# ZX_UNO_Aplus2.net
KiCad netlist of a schematic drawn in Altium Designer
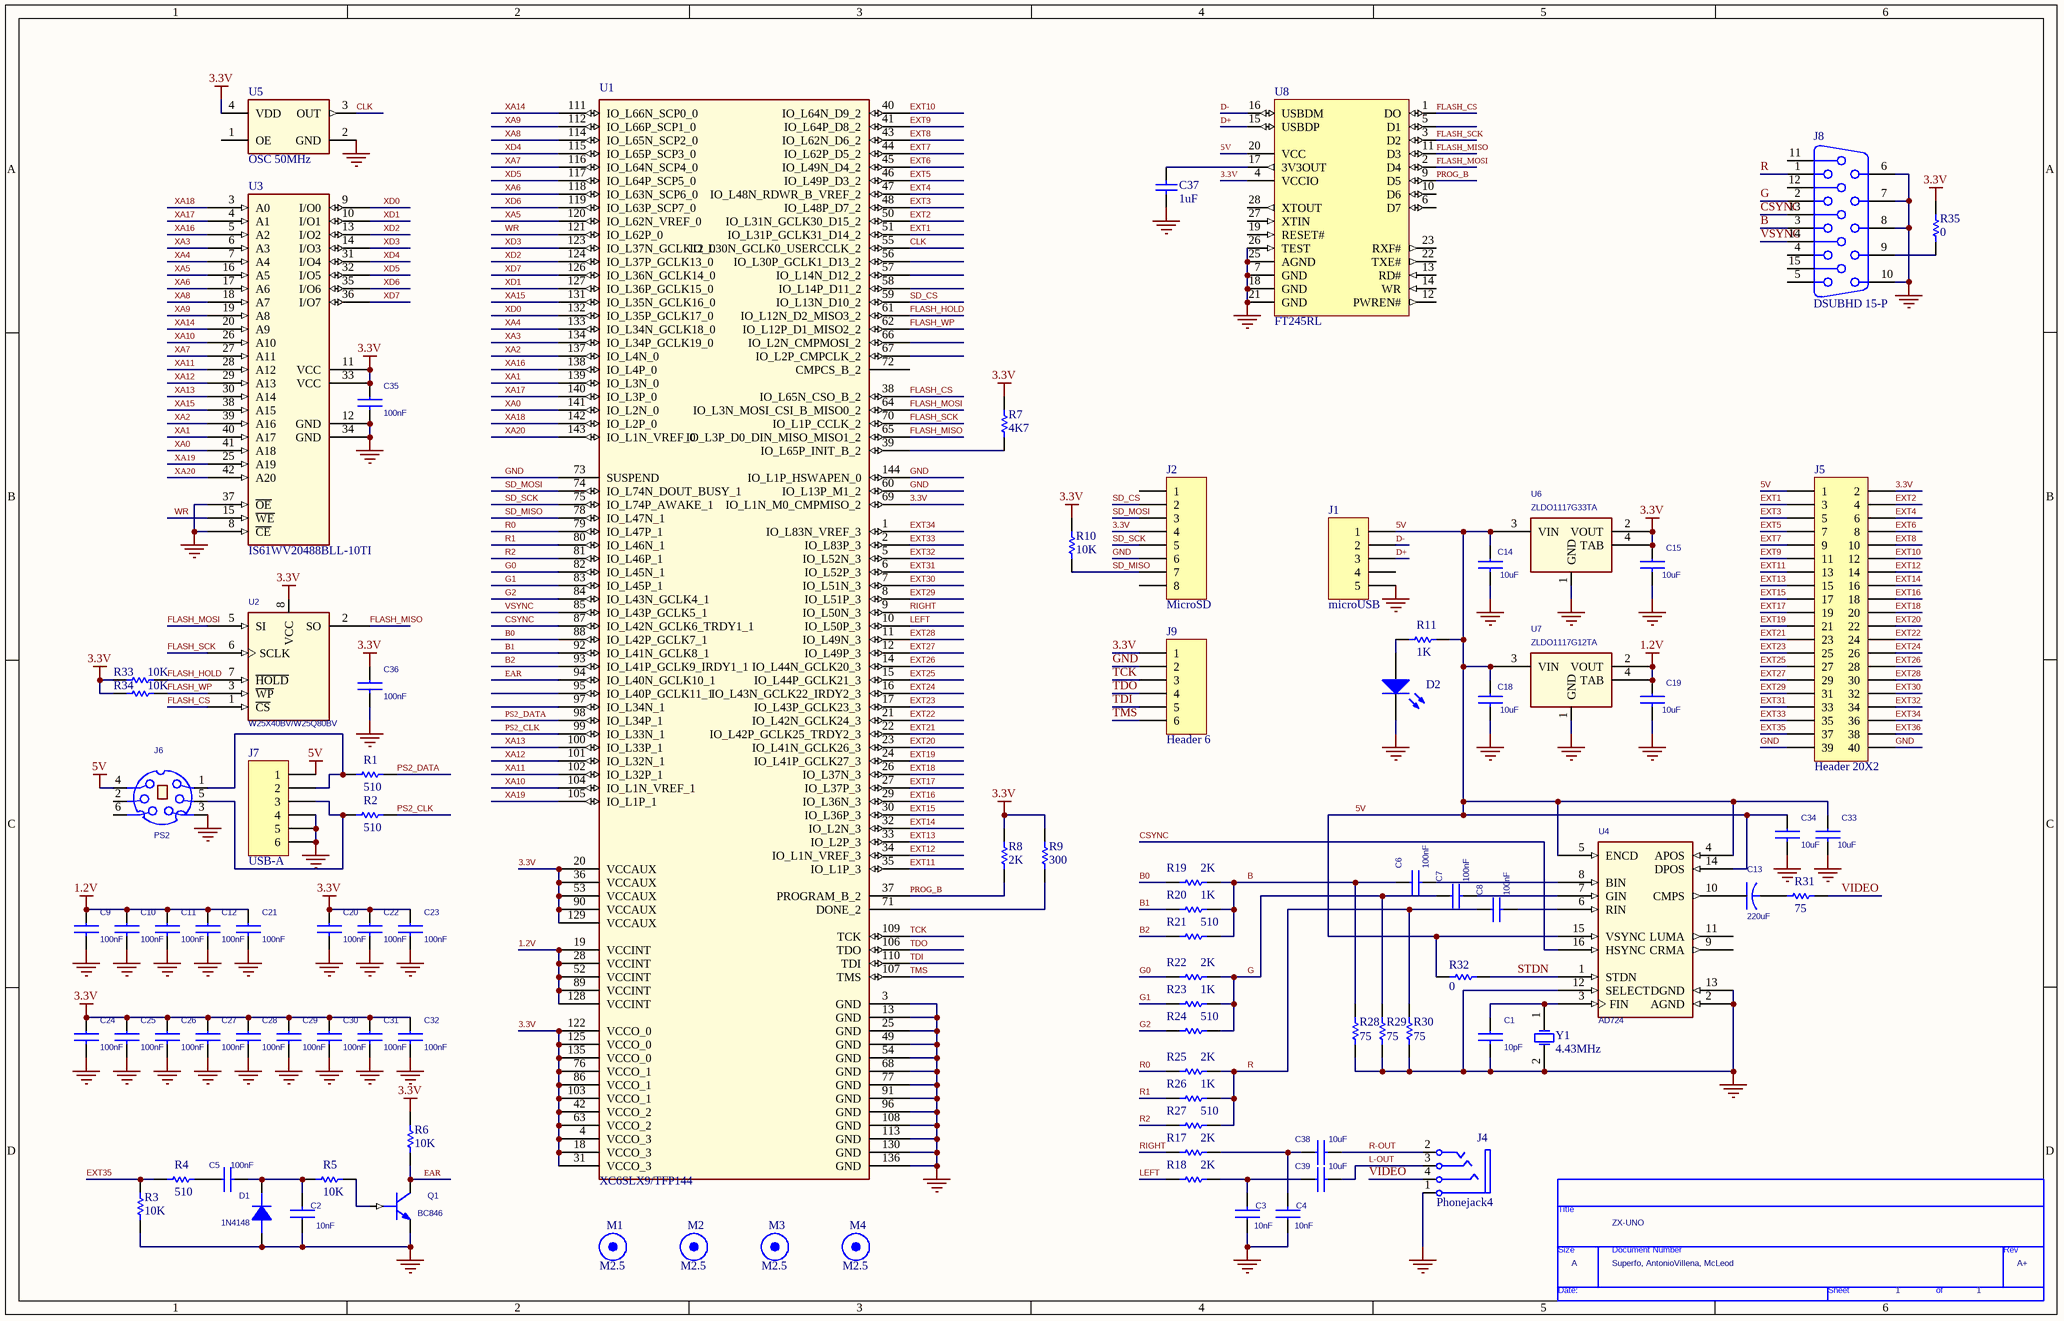
[diagram p0: ZX_UNO_Aplus2.SchDoc]

(export (version "E")
  (design (tool "Eeschema 10.0.6"))
  (components
    (comp (ref "*")
      (value "TitleBlock0")
      (fields
        (field (name "PAGE COUNT") "1")
        (field (name "PAGE NUMBER") "1")
        (field (name "PAGE SIZE") "A")
        (field (name "TITLE") "ZX-UNO")
        (field (name "REVCODE") "A+")
        (field (name "DOC") "Superfo, AntonioVillena, McLeod")
      )
      (libsource (lib "*") (part "TitleBlock0"))
    )
    (comp (ref "C1") (value "10pF") (libsource (lib "ZX_UNO_B") (part "CAP NP")))
    (comp (ref "C2") (value "10nF") (libsource (lib "ZX_UNO_B") (part "CAP NP")))
    (comp (ref "C3") (value "10nF") (libsource (lib "ZX_UNO_B") (part "CAP NP")))
    (comp (ref "C4") (value "10nF") (libsource (lib "ZX_UNO_B") (part "CAP NP")))
    (comp (ref "C5") (value "100nF") (libsource (lib "ZX_UNO_B") (part "CAP NP")))
    (comp (ref "C6") (value "100nF") (libsource (lib "ZX_UNO_B") (part "CAP NP")))
    (comp (ref "C7") (value "100nF") (libsource (lib "ZX_UNO_B") (part "CAP NP")))
    (comp (ref "C8") (value "100nF") (libsource (lib "ZX_UNO_B") (part "CAP NP")))
    (comp (ref "C9") (value "100nF") (libsource (lib "*") (part "CAP NP")))
    (comp (ref "C10") (value "100nF") (libsource (lib "*") (part "CAP NP")))
    (comp (ref "C11") (value "100nF") (libsource (lib "*") (part "CAP NP")))
    (comp (ref "C12") (value "100nF") (libsource (lib "*") (part "CAP NP")))
    (comp (ref "C13") (value "220uF") (libsource (lib "*") (part "CAP")))
    (comp (ref "C14") (value "10uF") (libsource (lib "*") (part "CAP NP")))
    (comp (ref "C15") (value "10uF") (libsource (lib "*") (part "CAP NP")))
    (comp (ref "C18") (value "10uF") (libsource (lib "*") (part "CAP NP")))
    (comp (ref "C19") (value "10uF") (libsource (lib "*") (part "CAP NP")))
    (comp (ref "C20") (value "100nF") (libsource (lib "*") (part "CAP NP")))
    (comp (ref "C21") (value "100nF") (libsource (lib "*") (part "CAP NP")))
    (comp (ref "C22") (value "100nF") (libsource (lib "*") (part "CAP NP")))
    (comp (ref "C23") (value "100nF") (libsource (lib "*") (part "CAP NP")))
    (comp (ref "C24") (value "100nF") (libsource (lib "*") (part "CAP NP")))
    (comp (ref "C25") (value "100nF") (libsource (lib "*") (part "CAP NP")))
    (comp (ref "C26") (value "100nF") (libsource (lib "*") (part "CAP NP")))
    (comp (ref "C27") (value "100nF") (libsource (lib "*") (part "CAP NP")))
    (comp (ref "C28") (value "100nF") (libsource (lib "*") (part "CAP NP")))
    (comp (ref "C29") (value "100nF") (libsource (lib "*") (part "CAP NP")))
    (comp (ref "C30") (value "100nF") (libsource (lib "*") (part "CAP NP")))
    (comp (ref "C31") (value "100nF") (libsource (lib "*") (part "CAP NP")))
    (comp (ref "C32") (value "100nF") (libsource (lib "*") (part "CAP NP")))
    (comp (ref "C33") (value "10uF") (libsource (lib "*") (part "CAP NP")))
    (comp (ref "C34") (value "10uF") (libsource (lib "*") (part "CAP NP")))
    (comp (ref "C35") (value "100nF") (libsource (lib "*") (part "CAP NP")))
    (comp (ref "C36") (value "100nF") (libsource (lib "*") (part "CAP NP")))
    (comp (ref "C37")
      (value "1uF")
      (footprint "SM/C_0805")
      (description "Capacitor")
      (fields (field (name "Comment") "Cap") (field (name "PUBLISHER") "Altium Limited"))
      (libsource (lib "Miscellaneous Devices") (part "Cap"))
    )
    (comp (ref "C38") (value "10uF") (libsource (lib "*") (part "CAP NP")))
    (comp (ref "C39") (value "10uF") (libsource (lib "*") (part "CAP NP")))
    (comp (ref "D1") (value "1N4148") (libsource (lib "*") (part "DIODE")))
    (comp (ref "D2")
      (value "LED0")
      (footprint "SM/LED_0603_21")
      (description "Typical INFRARED GaAs LED")
      (fields (field (name "PUBLISHER") "Altium Limited"))
      (libsource (lib "Miscellaneous Devices") (part "LED0"))
    )
    (comp (ref "J1")
      (value "microUSB")
      (footprint "MICRO USB")
      (description "Header, 5-Pin")
      (fields (field (name "PUBLISHER") "Altium Limited"))
      (libsource (lib "Miscellaneous Connectors") (part "Header 5"))
    )
    (comp (ref "J2")
      (value "MicroSD")
      (footprint "SD HR1941CT-ND")
      (description "Header, 8-Pin")
      (fields (field (name "PUBLISHER") "Altium Limited"))
      (libsource (lib "Miscellaneous Connectors") (part "Header 8"))
    )
    (comp (ref "J4")
      (value "Phonejack4")
      (footprint "AUDIO JACK PJ-322")
      (description "Jack Socket, 3.5mm, Thru-Hole, Right Angle, 4-Conductor")
      (fields (field (name "PUBLISHER") "Altium Limited"))
      (libsource (lib "Retro Computer") (part "Phonejack4"))
    )
    (comp (ref "J5")
      (value "Header 20X2")
      (footprint "HDR2X20")
      (description "Header, 20-Pin, Dual row")
      (fields (field (name "PUBLISHER") "Altium Limited"))
      (libsource (lib "Miscellaneous Connectors") (part "Header 20X2"))
    )
    (comp (ref "J6") (value "PS2") (libsource (lib "ZX_UNO_B") (part "M-DIN 8")))
    (comp (ref "J7")
      (value "USB-A")
      (footprint "USB A")
      (description "Header, 6-Pin")
      (fields (field (name "PUBLISHER") "Altium Limited"))
      (libsource (lib "") (part "Header 6_1"))
    )
    (comp (ref "J8")
      (value "DSUBHD 15-P")
      (footprint "DSUB/RP/SM/15")
      (description "Receptacle Assembly, 15-Pin, Sim Line Connector")
      (fields (field (name "PUBLISHER") "Altium Limited"))
      (libsource (lib "Misc Connectors 2") (part "DSUBHD 15-P"))
    )
    (comp (ref "J9")
      (value "Header 6")
      (footprint "HDR1X6")
      (description "Header, 6-Pin")
      (fields (field (name "PUBLISHER") "Altium Limited"))
      (libsource (lib "Miscellaneous Connectors") (part "Header 6"))
    )
    (comp (ref "M1") (value "M2.5") (footprint "M2.5") (libsource (lib "Misc Devices 2") (part "M2.5")))
    (comp (ref "M2") (value "M2.5") (footprint "M2.5") (libsource (lib "Misc Devices 2") (part "M2.5")))
    (comp (ref "M3") (value "M2.5") (footprint "M2.5") (libsource (lib "Misc Devices 2") (part "M2.5")))
    (comp (ref "M4") (value "M2.5") (footprint "M2.5") (libsource (lib "Misc Devices 2") (part "M2.5")))
    (comp (ref "Q1") (value "BC846") (libsource (lib "*") (part "BC547")))
    (comp (ref "R1")
      (value "510")
      (footprint "SM/R_0805")
      (description "Resistor")
      (fields (field (name "Comment") "Res1") (field (name "PUBLISHER") "Altium Limited"))
      (libsource (lib "Miscellaneous Devices") (part "Res1"))
    )
    (comp (ref "R2")
      (value "510")
      (footprint "SM/R_0805")
      (description "Resistor")
      (fields (field (name "Comment") "Res1") (field (name "PUBLISHER") "Altium Limited"))
      (libsource (lib "Miscellaneous Devices") (part "Res1"))
    )
    (comp (ref "R3")
      (value "10K")
      (footprint "SM/R_0805")
      (description "Resistor")
      (fields (field (name "Comment") "Res1") (field (name "PUBLISHER") "Altium Limited"))
      (libsource (lib "Miscellaneous Devices") (part "Res1"))
    )
    (comp (ref "R4")
      (value "510")
      (footprint "SM/R_0805")
      (description "Resistor")
      (fields (field (name "Comment") "Res1") (field (name "PUBLISHER") "Altium Limited"))
      (libsource (lib "Miscellaneous Devices") (part "Res1"))
    )
    (comp (ref "R5")
      (value "10K")
      (footprint "SM/R_0805")
      (description "Resistor")
      (fields (field (name "Comment") "Res1") (field (name "PUBLISHER") "Altium Limited"))
      (libsource (lib "Miscellaneous Devices") (part "Res1"))
    )
    (comp (ref "R6")
      (value "10K")
      (footprint "SM/R_0805")
      (description "Resistor")
      (fields (field (name "Comment") "Res1") (field (name "PUBLISHER") "Altium Limited"))
      (libsource (lib "Miscellaneous Devices") (part "Res1"))
    )
    (comp (ref "R7")
      (value "4K7")
      (footprint "SM/R_0805")
      (description "Resistor")
      (fields (field (name "Comment") "Res1") (field (name "PUBLISHER") "Altium Limited"))
      (libsource (lib "Miscellaneous Devices") (part "Res1"))
    )
    (comp (ref "R8")
      (value "2K")
      (footprint "SM/R_0805")
      (description "Resistor")
      (fields (field (name "Comment") "Res1") (field (name "PUBLISHER") "Altium Limited"))
      (libsource (lib "Miscellaneous Devices") (part "Res1"))
    )
    (comp (ref "R9")
      (value "300")
      (footprint "SM/R_0805")
      (description "Resistor")
      (fields (field (name "Comment") "Res1") (field (name "PUBLISHER") "Altium Limited"))
      (libsource (lib "Miscellaneous Devices") (part "Res1"))
    )
    (comp (ref "R10")
      (value "10K")
      (footprint "SM/R_0805")
      (description "Resistor")
      (fields (field (name "Comment") "Res1") (field (name "PUBLISHER") "Altium Limited"))
      (libsource (lib "Miscellaneous Devices") (part "Res1"))
    )
    (comp (ref "R11")
      (value "1K")
      (footprint "SM/R_0805")
      (description "Resistor")
      (fields (field (name "Comment") "Res1") (field (name "PUBLISHER") "Altium Limited"))
      (libsource (lib "Miscellaneous Devices") (part "Res1"))
    )
    (comp (ref "R17")
      (value "2K")
      (footprint "SM/R_0805")
      (description "Resistor")
      (fields (field (name "Comment") "Res1") (field (name "PUBLISHER") "Altium Limited"))
      (libsource (lib "Miscellaneous Devices") (part "Res1"))
    )
    (comp (ref "R18")
      (value "2K")
      (footprint "SM/R_0805")
      (description "Resistor")
      (fields (field (name "Comment") "Res1") (field (name "PUBLISHER") "Altium Limited"))
      (libsource (lib "Miscellaneous Devices") (part "Res1"))
    )
    (comp (ref "R19")
      (value "2K")
      (footprint "SM/R_0805")
      (description "Resistor")
      (fields (field (name "Comment") "Res1") (field (name "PUBLISHER") "Altium Limited"))
      (libsource (lib "Miscellaneous Devices") (part "Res1"))
    )
    (comp (ref "R20")
      (value "1K")
      (footprint "SM/R_0805")
      (description "Resistor")
      (fields (field (name "Comment") "Res1") (field (name "PUBLISHER") "Altium Limited"))
      (libsource (lib "Miscellaneous Devices") (part "Res1"))
    )
    (comp (ref "R21")
      (value "510")
      (footprint "SM/R_0805")
      (description "Resistor")
      (fields (field (name "Comment") "Res1") (field (name "PUBLISHER") "Altium Limited"))
      (libsource (lib "Miscellaneous Devices") (part "Res1"))
    )
    (comp (ref "R22")
      (value "2K")
      (footprint "SM/R_0805")
      (description "Resistor")
      (fields (field (name "Comment") "Res1") (field (name "PUBLISHER") "Altium Limited"))
      (libsource (lib "Miscellaneous Devices") (part "Res1"))
    )
    (comp (ref "R23")
      (value "1K")
      (footprint "SM/R_0805")
      (description "Resistor")
      (fields (field (name "Comment") "Res1") (field (name "PUBLISHER") "Altium Limited"))
      (libsource (lib "Miscellaneous Devices") (part "Res1"))
    )
    (comp (ref "R24")
      (value "510")
      (footprint "SM/R_0805")
      (description "Resistor")
      (fields (field (name "Comment") "Res1") (field (name "PUBLISHER") "Altium Limited"))
      (libsource (lib "Miscellaneous Devices") (part "Res1"))
    )
    (comp (ref "R25")
      (value "2K")
      (footprint "SM/R_0805")
      (description "Resistor")
      (fields (field (name "Comment") "Res1") (field (name "PUBLISHER") "Altium Limited"))
      (libsource (lib "Miscellaneous Devices") (part "Res1"))
    )
    (comp (ref "R26")
      (value "1K")
      (footprint "SM/R_0805")
      (description "Resistor")
      (fields (field (name "Comment") "Res1") (field (name "PUBLISHER") "Altium Limited"))
      (libsource (lib "Miscellaneous Devices") (part "Res1"))
    )
    (comp (ref "R27")
      (value "510")
      (footprint "SM/R_0805")
      (description "Resistor")
      (fields (field (name "Comment") "Res1") (field (name "PUBLISHER") "Altium Limited"))
      (libsource (lib "Miscellaneous Devices") (part "Res1"))
    )
    (comp (ref "R28")
      (value "75")
      (footprint "SM/R_0805")
      (description "Resistor")
      (fields (field (name "Comment") "Res1") (field (name "PUBLISHER") "Altium Limited"))
      (libsource (lib "Miscellaneous Devices") (part "Res1"))
    )
    (comp (ref "R29")
      (value "75")
      (footprint "SM/R_0805")
      (description "Resistor")
      (fields (field (name "Comment") "Res1") (field (name "PUBLISHER") "Altium Limited"))
      (libsource (lib "Miscellaneous Devices") (part "Res1"))
    )
    (comp (ref "R30")
      (value "75")
      (footprint "SM/R_0805")
      (description "Resistor")
      (fields (field (name "Comment") "Res1") (field (name "PUBLISHER") "Altium Limited"))
      (libsource (lib "Miscellaneous Devices") (part "Res1"))
    )
    (comp (ref "R31")
      (value "75")
      (footprint "SM/R_0805")
      (description "Resistor")
      (fields (field (name "Comment") "Res1") (field (name "PUBLISHER") "Altium Limited"))
      (libsource (lib "Miscellaneous Devices") (part "Res1"))
    )
    (comp (ref "R32")
      (value "0")
      (footprint "SM/R_0805")
      (description "Resistor")
      (fields (field (name "Comment") "Res1") (field (name "PUBLISHER") "Altium Limited"))
      (libsource (lib "Miscellaneous Devices") (part "Res1"))
    )
    (comp (ref "R33")
      (value "10K")
      (footprint "SM/R_0805")
      (description "Resistor")
      (fields (field (name "Comment") "Res1") (field (name "PUBLISHER") "Altium Limited"))
      (libsource (lib "Miscellaneous Devices") (part "Res1"))
    )
    (comp (ref "R34")
      (value "10K")
      (footprint "SM/R_0805")
      (description "Resistor")
      (fields (field (name "Comment") "Res1") (field (name "PUBLISHER") "Altium Limited"))
      (libsource (lib "Miscellaneous Devices") (part "Res1"))
    )
    (comp (ref "R35")
      (value "0")
      (footprint "SM/R_0805")
      (description "Resistor")
      (fields (field (name "Comment") "Res1") (field (name "PUBLISHER") "Altium Limited"))
      (libsource (lib "Miscellaneous Devices") (part "Res1"))
    )
    (comp (ref "U1") (value "XC6SLX9/TFP144") (libsource (lib "ZX_UNO_B") (part "XC6SLX9/TFP144")))
    (comp (ref "U2") (value "W25X40BV/W25Q80BV") (libsource (lib "ZX_UNO_B") (part "FLASH-25XX")))
    (comp (ref "U3")
      (value "IS61WV20488BLL-10TI")
      (footprint "SOP80P1176-44M")
      (libsource (lib "ZX_UNO_Library") (part "IS61WV20488BLL-10TI"))
    )
    (comp (ref "U4") (value "AD724") (libsource (lib "*") (part "AD724")))
    (comp (ref "U5") (value "OSC 50MHz") (footprint "SM/OSC") (libsource (lib "Misc Devices 2") (part "OSC")))
    (comp (ref "U6")
      (value "ZLDO1117G33TA")
      (footprint "SM/SOT223")
      (libsource (lib "ZX_UNO_B") (part "REGULATOR-1"))
    )
    (comp (ref "U7")
      (value "ZLDO1117G12TA")
      (footprint "SM/SOT223")
      (libsource (lib "ZX_UNO_B") (part "REGULATOR-1"))
    )
    (comp (ref "U8")
      (value "FT245RL")
      (footprint "SOP_65P_N:SOP65P780-28N")
      (description "USB/Parallel FIFO Bi-Directional Data Transfer Chip, LQFP-32, Pb-Free")
      (fields (field (name "PUBLISHER") "Altium Limited"))
      (libsource (lib "Misc Devices 2") (part "FT245RL"))
    )
    (comp (ref "Y1")
      (value "4.43MHz")
      (footprint "XTAL")
      (description "Crystal Oscillator")
      (fields (field (name "PUBLISHER") "Altium Limited"))
      (libsource (lib "Miscellaneous Devices") (part "XTAL"))
    )
  )
  (nets
    (net (code "1") (name "/B") (class "Default")
      (node (ref "C6") (pin "1") (pinfunction "1_1") (pintype "passive"))
      (node (ref "J8") (pin "3") (pinfunction "3_3") (pintype "passive"))
      (node (ref "R19") (pin "2") (pinfunction "2_2") (pintype "passive"))
      (node (ref "R20") (pin "2") (pinfunction "2_2") (pintype "passive"))
      (node (ref "R21") (pin "2") (pinfunction "2_2") (pintype "passive"))
      (node (ref "R28") (pin "2") (pinfunction "2_2") (pintype "passive"))
    )
    (net (code "2") (name "/B0") (class "Default")
      (node (ref "R19") (pin "1") (pinfunction "1_1") (pintype "passive"))
      (node (ref "U1") (pin "88") (pinfunction "IO_L42P_GCLK7_1_88") (pintype "bidirectional"))
    )
    (net (code "3") (name "/B1") (class "Default")
      (node (ref "R20") (pin "1") (pinfunction "1_1") (pintype "passive"))
      (node (ref "U1") (pin "92") (pinfunction "IO_L41N_GCLK8_1_92") (pintype "bidirectional"))
    )
    (net (code "4") (name "/B2") (class "Default")
      (node (ref "R21") (pin "1") (pinfunction "1_1") (pintype "passive"))
      (node (ref "U1") (pin "93") (pinfunction "IO_L41P_GCLK9_IRDY1_1_93") (pintype "bidirectional"))
    )
    (net (code "5") (name "/CLK") (class "Default")
      (node (ref "U1") (pin "55") (pinfunction "IO_L30N_GCLK0_USERCCLK_2_55") (pintype "bidirectional"))
      (node (ref "U5") (pin "3") (pinfunction "OUT_3") (pintype "output"))
    )
    (net (code "6") (name "/CSYNC") (class "Default")
      (node (ref "J8") (pin "13") (pinfunction "13_13") (pintype "passive"))
      (node (ref "U1") (pin "87") (pinfunction "IO_L42N_GCLK6_TRDY1_1_87") (pintype "bidirectional"))
      (node (ref "U4") (pin "16") (pinfunction "HSYNC_16") (pintype "input"))
    )
    (net (code "7") (name "/D+") (class "Default")
      (node (ref "J1") (pin "3") (pinfunction "3_3") (pintype "passive"))
      (node (ref "U8") (pin "15") (pinfunction "USBDP_15") (pintype "bidirectional"))
    )
    (net (code "8") (name "/D-") (class "Default")
      (node (ref "J1") (pin "2") (pinfunction "2_2") (pintype "passive"))
      (node (ref "U8") (pin "16") (pinfunction "USBDM_16") (pintype "bidirectional"))
    )
    (net (code "9") (name "/EAR") (class "Default")
      (node (ref "Q1") (pin "1") (pinfunction "COLLECTOR_1") (pintype "passive"))
      (node (ref "R6") (pin "2") (pinfunction "2_2") (pintype "passive"))
      (node (ref "U1") (pin "94") (pinfunction "IO_L40N_GCLK10_1_94") (pintype "bidirectional"))
    )
    (net (code "10") (name "/EXT1") (class "Default")
      (node (ref "J5") (pin "3") (pinfunction "3_3") (pintype "passive"))
      (node (ref "U1") (pin "51") (pinfunction "IO_L31P_GCLK31_D14_2_51") (pintype "bidirectional"))
    )
    (net (code "11") (name "/EXT2") (class "Default")
      (node (ref "J5") (pin "4") (pinfunction "4_4") (pintype "passive"))
      (node (ref "U1") (pin "50") (pinfunction "IO_L31N_GCLK30_D15_2_50") (pintype "bidirectional"))
    )
    (net (code "12") (name "/EXT3") (class "Default")
      (node (ref "J5") (pin "5") (pinfunction "5_5") (pintype "passive"))
      (node (ref "U1") (pin "48") (pinfunction "IO_L48P_D7_2_48") (pintype "bidirectional"))
    )
    (net (code "13") (name "/EXT4") (class "Default")
      (node (ref "J5") (pin "6") (pinfunction "6_6") (pintype "passive"))
      (node (ref "U1") (pin "47") (pinfunction "IO_L48N_RDWR_B_VREF_2_47") (pintype "bidirectional"))
    )
    (net (code "14") (name "/EXT5") (class "Default")
      (node (ref "J5") (pin "7") (pinfunction "7_7") (pintype "passive"))
      (node (ref "U1") (pin "46") (pinfunction "IO_L49P_D3_2_46") (pintype "bidirectional"))
    )
    (net (code "15") (name "/EXT6") (class "Default")
      (node (ref "J5") (pin "8") (pinfunction "8_8") (pintype "passive"))
      (node (ref "U1") (pin "45") (pinfunction "IO_L49N_D4_2_45") (pintype "bidirectional"))
    )
    (net (code "16") (name "/EXT7") (class "Default")
      (node (ref "J5") (pin "9") (pinfunction "9_9") (pintype "passive"))
      (node (ref "U1") (pin "44") (pinfunction "IO_L62P_D5_2_44") (pintype "bidirectional"))
    )
    (net (code "17") (name "/EXT8") (class "Default")
      (node (ref "J5") (pin "10") (pinfunction "10_10") (pintype "passive"))
      (node (ref "U1") (pin "43") (pinfunction "IO_L62N_D6_2_43") (pintype "bidirectional"))
    )
    (net (code "18") (name "/EXT9") (class "Default")
      (node (ref "J5") (pin "11") (pinfunction "11_11") (pintype "passive"))
      (node (ref "U1") (pin "41") (pinfunction "IO_L64P_D8_2_41") (pintype "bidirectional"))
    )
    (net (code "19") (name "/EXT10") (class "Default")
      (node (ref "J5") (pin "12") (pinfunction "12_12") (pintype "passive"))
      (node (ref "U1") (pin "40") (pinfunction "IO_L64N_D9_2_40") (pintype "bidirectional"))
    )
    (net (code "20") (name "/EXT11") (class "Default")
      (node (ref "J5") (pin "13") (pinfunction "13_13") (pintype "passive"))
      (node (ref "U1") (pin "35") (pinfunction "IO_L1P_3_35") (pintype "bidirectional"))
    )
    (net (code "21") (name "/EXT12") (class "Default")
      (node (ref "J5") (pin "14") (pinfunction "14_14") (pintype "passive"))
      (node (ref "U1") (pin "34") (pinfunction "IO_L1N_VREF_3_34") (pintype "bidirectional"))
    )
    (net (code "22") (name "/EXT13") (class "Default")
      (node (ref "J5") (pin "15") (pinfunction "15_15") (pintype "passive"))
      (node (ref "U1") (pin "33") (pinfunction "IO_L2P_3_33") (pintype "bidirectional"))
    )
    (net (code "23") (name "/EXT14") (class "Default")
      (node (ref "J5") (pin "16") (pinfunction "16_16") (pintype "passive"))
      (node (ref "U1") (pin "32") (pinfunction "IO_L2N_3_32") (pintype "bidirectional"))
    )
    (net (code "24") (name "/EXT15") (class "Default")
      (node (ref "J5") (pin "17") (pinfunction "17_17") (pintype "passive"))
      (node (ref "U1") (pin "30") (pinfunction "IO_L36P_3_30") (pintype "bidirectional"))
    )
    (net (code "25") (name "/EXT16") (class "Default")
      (node (ref "J5") (pin "18") (pinfunction "18_18") (pintype "passive"))
      (node (ref "U1") (pin "29") (pinfunction "IO_L36N_3_29") (pintype "bidirectional"))
    )
    (net (code "26") (name "/EXT17") (class "Default")
      (node (ref "J5") (pin "19") (pinfunction "19_19") (pintype "passive"))
      (node (ref "U1") (pin "27") (pinfunction "IO_L37P_3_27") (pintype "bidirectional"))
    )
    (net (code "27") (name "/EXT18") (class "Default")
      (node (ref "J5") (pin "20") (pinfunction "20_20") (pintype "passive"))
      (node (ref "U1") (pin "26") (pinfunction "IO_L37N_3_26") (pintype "bidirectional"))
    )
    (net (code "28") (name "/EXT19") (class "Default")
      (node (ref "J5") (pin "21") (pinfunction "21_21") (pintype "passive"))
      (node (ref "U1") (pin "24") (pinfunction "IO_L41P_GCLK27_3_24") (pintype "bidirectional"))
    )
    (net (code "29") (name "/EXT20") (class "Default")
      (node (ref "J5") (pin "22") (pinfunction "22_22") (pintype "passive"))
      (node (ref "U1") (pin "23") (pinfunction "IO_L41N_GCLK26_3_23") (pintype "bidirectional"))
    )
    (net (code "30") (name "/EXT21") (class "Default")
      (node (ref "J5") (pin "23") (pinfunction "23_23") (pintype "passive"))
      (node (ref "U1") (pin "22") (pinfunction "IO_L42P_GCLK25_TRDY2_3_22") (pintype "bidirectional"))
    )
    (net (code "31") (name "/EXT22") (class "Default")
      (node (ref "J5") (pin "24") (pinfunction "24_24") (pintype "passive"))
      (node (ref "U1") (pin "21") (pinfunction "IO_L42N_GCLK24_3_21") (pintype "bidirectional"))
    )
    (net (code "32") (name "/EXT23") (class "Default")
      (node (ref "J5") (pin "25") (pinfunction "25_25") (pintype "passive"))
      (node (ref "U1") (pin "17") (pinfunction "IO_L43P_GCLK23_3_17") (pintype "bidirectional"))
    )
    (net (code "33") (name "/EXT24") (class "Default")
      (node (ref "J5") (pin "26") (pinfunction "26_26") (pintype "passive"))
      (node (ref "U1") (pin "16") (pinfunction "IO_L43N_GCLK22_IRDY2_3_16") (pintype "bidirectional"))
    )
    (net (code "34") (name "/EXT25") (class "Default")
      (node (ref "J5") (pin "27") (pinfunction "27_27") (pintype "passive"))
      (node (ref "U1") (pin "15") (pinfunction "IO_L44P_GCLK21_3_15") (pintype "bidirectional"))
    )
    (net (code "35") (name "/EXT26") (class "Default")
      (node (ref "J5") (pin "28") (pinfunction "28_28") (pintype "passive"))
      (node (ref "U1") (pin "14") (pinfunction "IO_L44N_GCLK20_3_14") (pintype "bidirectional"))
    )
    (net (code "36") (name "/EXT27") (class "Default")
      (node (ref "J5") (pin "29") (pinfunction "29_29") (pintype "passive"))
      (node (ref "U1") (pin "12") (pinfunction "IO_L49P_3_12") (pintype "bidirectional"))
    )
    (net (code "37") (name "/EXT28") (class "Default")
      (node (ref "J5") (pin "30") (pinfunction "30_30") (pintype "passive"))
      (node (ref "U1") (pin "11") (pinfunction "IO_L49N_3_11") (pintype "bidirectional"))
    )
    (net (code "38") (name "/EXT29") (class "Default")
      (node (ref "J5") (pin "31") (pinfunction "31_31") (pintype "passive"))
      (node (ref "U1") (pin "8") (pinfunction "IO_L51P_3_8") (pintype "bidirectional"))
    )
    (net (code "39") (name "/EXT30") (class "Default")
      (node (ref "J5") (pin "32") (pinfunction "32_32") (pintype "passive"))
      (node (ref "U1") (pin "7") (pinfunction "IO_L51N_3_7") (pintype "bidirectional"))
    )
    (net (code "40") (name "/EXT31") (class "Default")
      (node (ref "J5") (pin "33") (pinfunction "33_33") (pintype "passive"))
      (node (ref "U1") (pin "6") (pinfunction "IO_L52P_3_6") (pintype "bidirectional"))
    )
    (net (code "41") (name "/EXT32") (class "Default")
      (node (ref "J5") (pin "34") (pinfunction "34_34") (pintype "passive"))
      (node (ref "U1") (pin "5") (pinfunction "IO_L52N_3_5") (pintype "bidirectional"))
    )
    (net (code "42") (name "/EXT33") (class "Default")
      (node (ref "J5") (pin "35") (pinfunction "35_35") (pintype "passive"))
      (node (ref "U1") (pin "2") (pinfunction "IO_L83P_3_2") (pintype "bidirectional"))
    )
    (net (code "43") (name "/EXT34") (class "Default")
      (node (ref "J5") (pin "36") (pinfunction "36_36") (pintype "passive"))
      (node (ref "U1") (pin "1") (pinfunction "IO_L83N_VREF_3_1") (pintype "bidirectional"))
    )
    (net (code "44") (name "/EXT35") (class "Default")
      (node (ref "J5") (pin "37") (pinfunction "37_37") (pintype "passive"))
      (node (ref "R3") (pin "1") (pinfunction "1_1") (pintype "passive"))
      (node (ref "R4") (pin "1") (pinfunction "1_1") (pintype "passive"))
    )
    (net (code "45") (name "/EXT36") (class "Default")
      (node (ref "J5") (pin "38") (pinfunction "38_38") (pintype "passive"))
    )
    (net (code "46") (name "/FLASH_CS") (class "Default")
      (node (ref "U1") (pin "38") (pinfunction "IO_L65N_CSO_B_2_38") (pintype "bidirectional"))
      (node (ref "U2") (pin "1") (pinfunction "~{CS}_1") (pintype "input"))
      (node (ref "U8") (pin "1") (pinfunction "DO_1") (pintype "bidirectional"))
    )
    (net (code "47") (name "/FLASH_HOLD") (class "Default")
      (node (ref "R33") (pin "2") (pinfunction "2_2") (pintype "passive"))
      (node (ref "U1") (pin "61") (pinfunction "IO_L12N_D2_MISO3_2_61") (pintype "bidirectional"))
      (node (ref "U2") (pin "7") (pinfunction "~{HOLD}_7") (pintype "input"))
    )
    (net (code "48") (name "/FLASH_MISO") (class "Default")
      (node (ref "U1") (pin "65") (pinfunction "IO_L3P_D0_DIN_MISO_MISO1_2_65") (pintype "bidirectional"))
      (node (ref "U2") (pin "2") (pinfunction "SO_2") (pintype "tri_state"))
      (node (ref "U8") (pin "11") (pinfunction "D3_11") (pintype "bidirectional"))
    )
    (net (code "49") (name "/FLASH_MOSI") (class "Default")
      (node (ref "U1") (pin "64") (pinfunction "IO_L3N_MOSI_CSI_B_MISO0_2_64") (pintype "bidirectional"))
      (node (ref "U2") (pin "5") (pinfunction "SI_5") (pintype "input"))
      (node (ref "U8") (pin "2") (pinfunction "D4_2") (pintype "bidirectional"))
    )
    (net (code "50") (name "/FLASH_SCK") (class "Default")
      (node (ref "U1") (pin "70") (pinfunction "IO_L1P_CCLK_2_70") (pintype "bidirectional"))
      (node (ref "U2") (pin "6") (pinfunction "SCLK_6") (pintype "input"))
      (node (ref "U8") (pin "3") (pinfunction "D2_3") (pintype "bidirectional"))
    )
    (net (code "51") (name "/FLASH_WP") (class "Default")
      (node (ref "R34") (pin "2") (pinfunction "2_2") (pintype "passive"))
      (node (ref "U1") (pin "62") (pinfunction "IO_L12P_D1_MISO2_2_62") (pintype "bidirectional"))
      (node (ref "U2") (pin "3") (pinfunction "~{WP}_3") (pintype "input"))
    )
    (net (code "52") (name "/G") (class "Default")
      (node (ref "C7") (pin "1") (pinfunction "1_1") (pintype "passive"))
      (node (ref "J8") (pin "2") (pinfunction "2_2") (pintype "passive"))
      (node (ref "R22") (pin "2") (pinfunction "2_2") (pintype "passive"))
      (node (ref "R23") (pin "2") (pinfunction "2_2") (pintype "passive"))
      (node (ref "R24") (pin "2") (pinfunction "2_2") (pintype "passive"))
      (node (ref "R29") (pin "2") (pinfunction "2_2") (pintype "passive"))
    )
    (net (code "53") (name "/G0") (class "Default")
      (node (ref "R22") (pin "1") (pinfunction "1_1") (pintype "passive"))
      (node (ref "U1") (pin "82") (pinfunction "IO_L45N_1_82") (pintype "bidirectional"))
    )
    (net (code "54") (name "/G1") (class "Default")
      (node (ref "R23") (pin "1") (pinfunction "1_1") (pintype "passive"))
      (node (ref "U1") (pin "83") (pinfunction "IO_L45P_1_83") (pintype "bidirectional"))
    )
    (net (code "55") (name "/G2") (class "Default")
      (node (ref "R24") (pin "1") (pinfunction "1_1") (pintype "passive"))
      (node (ref "U1") (pin "84") (pinfunction "IO_L43N_GCLK4_1_84") (pintype "bidirectional"))
    )
    (net (code "56") (name "/L-OUT") (class "Default")
      (node (ref "C39") (pin "2") (pinfunction "2_2") (pintype "passive"))
      (node (ref "J4") (pin "3") (pinfunction "RN_3") (pintype "passive"))
    )
    (net (code "57") (name "/LEFT") (class "Default")
      (node (ref "R18") (pin "1") (pinfunction "1_1") (pintype "passive"))
      (node (ref "U1") (pin "10") (pinfunction "IO_L50P_3_10") (pintype "bidirectional"))
    )
    (net (code "58") (name "/PROG_B") (class "Default")
      (node (ref "R8") (pin "1") (pinfunction "1_1") (pintype "passive"))
      (node (ref "U1") (pin "37") (pinfunction "PROGRAM_B_2_37") (pintype "passive"))
      (node (ref "U8") (pin "9") (pinfunction "D5_9") (pintype "bidirectional"))
    )
    (net (code "59") (name "/PS2_CLK") (class "Default")
      (node (ref "R2") (pin "2") (pinfunction "2_2") (pintype "passive"))
      (node (ref "U1") (pin "99") (pinfunction "IO_L33N_1_99") (pintype "bidirectional"))
    )
    (net (code "60") (name "/PS2_DATA") (class "Default")
      (node (ref "R1") (pin "2") (pinfunction "2_2") (pintype "passive"))
      (node (ref "U1") (pin "98") (pinfunction "IO_L34P_1_98") (pintype "bidirectional"))
    )
    (net (code "61") (name "/R") (class "Default")
      (node (ref "C8") (pin "1") (pinfunction "1_1") (pintype "passive"))
      (node (ref "J8") (pin "1") (pinfunction "1_1") (pintype "passive"))
      (node (ref "R25") (pin "2") (pinfunction "2_2") (pintype "passive"))
      (node (ref "R26") (pin "2") (pinfunction "2_2") (pintype "passive"))
      (node (ref "R27") (pin "2") (pinfunction "2_2") (pintype "passive"))
      (node (ref "R30") (pin "2") (pinfunction "2_2") (pintype "passive"))
    )
    (net (code "62") (name "/R-OUT") (class "Default")
      (node (ref "C38") (pin "2") (pinfunction "2_2") (pintype "passive"))
      (node (ref "J4") (pin "2") (pinfunction "T_2") (pintype "passive"))
    )
    (net (code "63") (name "/R0") (class "Default")
      (node (ref "R25") (pin "1") (pinfunction "1_1") (pintype "passive"))
      (node (ref "U1") (pin "79") (pinfunction "IO_L47P_1_79") (pintype "bidirectional"))
    )
    (net (code "64") (name "/R1") (class "Default")
      (node (ref "R26") (pin "1") (pinfunction "1_1") (pintype "passive"))
      (node (ref "U1") (pin "80") (pinfunction "IO_L46N_1_80") (pintype "bidirectional"))
    )
    (net (code "65") (name "/R2") (class "Default")
      (node (ref "R27") (pin "1") (pinfunction "1_1") (pintype "passive"))
      (node (ref "U1") (pin "81") (pinfunction "IO_L46P_1_81") (pintype "bidirectional"))
    )
    (net (code "66") (name "/RIGHT") (class "Default")
      (node (ref "R17") (pin "1") (pinfunction "1_1") (pintype "passive"))
      (node (ref "U1") (pin "9") (pinfunction "IO_L50N_3_9") (pintype "bidirectional"))
    )
    (net (code "67") (name "/SD_CS") (class "Default")
      (node (ref "J2") (pin "2") (pinfunction "2_2") (pintype "passive"))
      (node (ref "U1") (pin "59") (pinfunction "IO_L13N_D10_2_59") (pintype "bidirectional"))
    )
    (net (code "68") (name "/SD_MISO") (class "Default")
      (node (ref "J2") (pin "7") (pinfunction "7_7") (pintype "passive"))
      (node (ref "R10") (pin "1") (pinfunction "1_1") (pintype "passive"))
      (node (ref "U1") (pin "78") (pinfunction "IO_L47N_1_78") (pintype "bidirectional"))
    )
    (net (code "69") (name "/SD_MOSI") (class "Default")
      (node (ref "J2") (pin "3") (pinfunction "3_3") (pintype "passive"))
      (node (ref "U1") (pin "74") (pinfunction "IO_L74N_DOUT_BUSY_1_74") (pintype "bidirectional"))
    )
    (net (code "70") (name "/SD_SCK") (class "Default")
      (node (ref "J2") (pin "5") (pinfunction "5_5") (pintype "passive"))
      (node (ref "U1") (pin "75") (pinfunction "IO_L74P_AWAKE_1_75") (pintype "bidirectional"))
    )
    (net (code "71") (name "/STDN") (class "Default")
      (node (ref "R32") (pin "1") (pinfunction "1_1") (pintype "passive"))
      (node (ref "U4") (pin "1") (pinfunction "STDN_1") (pintype "input"))
    )
    (net (code "72") (name "/TCK") (class "Default")
      (node (ref "J9") (pin "3") (pinfunction "3_3") (pintype "passive"))
      (node (ref "U1") (pin "109") (pinfunction "TCK_109") (pintype "bidirectional"))
    )
    (net (code "73") (name "/TDI") (class "Default")
      (node (ref "J9") (pin "5") (pinfunction "5_5") (pintype "passive"))
      (node (ref "U1") (pin "110") (pinfunction "TDI_110") (pintype "bidirectional"))
    )
    (net (code "74") (name "/TDO") (class "Default")
      (node (ref "J9") (pin "4") (pinfunction "4_4") (pintype "passive"))
      (node (ref "U1") (pin "106") (pinfunction "TDO_106") (pintype "bidirectional"))
    )
    (net (code "75") (name "/TMS") (class "Default")
      (node (ref "J9") (pin "6") (pinfunction "6_6") (pintype "passive"))
      (node (ref "U1") (pin "107") (pinfunction "TMS_107") (pintype "bidirectional"))
    )
    (net (code "76") (name "/VIDEO") (class "Default")
      (node (ref "J4") (pin "4") (pinfunction "R_4") (pintype "passive"))
      (node (ref "R31") (pin "2") (pinfunction "2_2") (pintype "passive"))
    )
    (net (code "77") (name "/VSYNC") (class "Default")
      (node (ref "J8") (pin "14") (pinfunction "14_14") (pintype "passive"))
      (node (ref "U1") (pin "85") (pinfunction "IO_L43P_GCLK5_1_85") (pintype "bidirectional"))
    )
    (net (code "78") (name "/WR") (class "Default")
      (node (ref "U1") (pin "121") (pinfunction "IO_L62P_0_121") (pintype "bidirectional"))
      (node (ref "U3") (pin "15") (pinfunction "~{WE}_15") (pintype "input"))
    )
    (net (code "79") (name "/XA0") (class "Default")
      (node (ref "U1") (pin "141") (pinfunction "IO_L2N_0_141") (pintype "bidirectional"))
      (node (ref "U3") (pin "41") (pinfunction "A18_41") (pintype "input"))
    )
    (net (code "80") (name "/XA1") (class "Default")
      (node (ref "U1") (pin "139") (pinfunction "IO_L3N_0_139") (pintype "bidirectional"))
      (node (ref "U3") (pin "40") (pinfunction "A17_40") (pintype "input"))
    )
    (net (code "81") (name "/XA2") (class "Default")
      (node (ref "U1") (pin "137") (pinfunction "IO_L4N_0_137") (pintype "bidirectional"))
      (node (ref "U3") (pin "39") (pinfunction "A16_39") (pintype "input"))
    )
    (net (code "82") (name "/XA3") (class "Default")
      (node (ref "U1") (pin "134") (pinfunction "IO_L34P_GCLK19_0_134") (pintype "bidirectional"))
      (node (ref "U3") (pin "6") (pinfunction "A3_6") (pintype "input"))
    )
    (net (code "83") (name "/XA4") (class "Default")
      (node (ref "U1") (pin "133") (pinfunction "IO_L34N_GCLK18_0_133") (pintype "bidirectional"))
      (node (ref "U3") (pin "7") (pinfunction "A4_7") (pintype "input"))
    )
    (net (code "84") (name "/XA5") (class "Default")
      (node (ref "U1") (pin "120") (pinfunction "IO_L62N_VREF_0_120") (pintype "bidirectional"))
      (node (ref "U3") (pin "16") (pinfunction "A5_16") (pintype "input"))
    )
    (net (code "85") (name "/XA6") (class "Default")
      (node (ref "U1") (pin "118") (pinfunction "IO_L63N_SCP6_0_118") (pintype "bidirectional"))
      (node (ref "U3") (pin "17") (pinfunction "A6_17") (pintype "input"))
    )
    (net (code "86") (name "/XA7") (class "Default")
      (node (ref "U1") (pin "116") (pinfunction "IO_L64N_SCP4_0_116") (pintype "bidirectional"))
      (node (ref "U3") (pin "27") (pinfunction "A11_27") (pintype "input"))
    )
    (net (code "87") (name "/XA8") (class "Default")
      (node (ref "U1") (pin "114") (pinfunction "IO_L65N_SCP2_0_114") (pintype "bidirectional"))
      (node (ref "U3") (pin "18") (pinfunction "A7_18") (pintype "input"))
    )
    (net (code "88") (name "/XA9") (class "Default")
      (node (ref "U1") (pin "112") (pinfunction "IO_L66P_SCP1_0_112") (pintype "bidirectional"))
      (node (ref "U3") (pin "19") (pinfunction "A8_19") (pintype "input"))
    )
    (net (code "89") (name "/XA10") (class "Default")
      (node (ref "U1") (pin "104") (pinfunction "IO_L1N_VREF_1_104") (pintype "bidirectional"))
      (node (ref "U3") (pin "26") (pinfunction "A10_26") (pintype "input"))
    )
    (net (code "90") (name "/XA11") (class "Default")
      (node (ref "U1") (pin "102") (pinfunction "IO_L32P_1_102") (pintype "bidirectional"))
      (node (ref "U3") (pin "28") (pinfunction "A12_28") (pintype "input"))
    )
    (net (code "91") (name "/XA12") (class "Default")
      (node (ref "U1") (pin "101") (pinfunction "IO_L32N_1_101") (pintype "bidirectional"))
      (node (ref "U3") (pin "29") (pinfunction "A13_29") (pintype "input"))
    )
    (net (code "92") (name "/XA13") (class "Default")
      (node (ref "U1") (pin "100") (pinfunction "IO_L33P_1_100") (pintype "bidirectional"))
      (node (ref "U3") (pin "30") (pinfunction "A14_30") (pintype "input"))
    )
    (net (code "93") (name "/XA14") (class "Default")
      (node (ref "U1") (pin "111") (pinfunction "IO_L66N_SCP0_0_111") (pintype "bidirectional"))
      (node (ref "U3") (pin "20") (pinfunction "A9_20") (pintype "input"))
    )
    (net (code "94") (name "/XA15") (class "Default")
      (node (ref "U1") (pin "131") (pinfunction "IO_L35N_GCLK16_0_131") (pintype "bidirectional"))
      (node (ref "U3") (pin "38") (pinfunction "A15_38") (pintype "input"))
    )
    (net (code "95") (name "/XA16") (class "Default")
      (node (ref "U1") (pin "138") (pinfunction "IO_L4P_0_138") (pintype "bidirectional"))
      (node (ref "U3") (pin "5") (pinfunction "A2_5") (pintype "input"))
    )
    (net (code "96") (name "/XA17") (class "Default")
      (node (ref "U1") (pin "140") (pinfunction "IO_L3P_0_140") (pintype "bidirectional"))
      (node (ref "U3") (pin "4") (pinfunction "A1_4") (pintype "input"))
    )
    (net (code "97") (name "/XA18") (class "Default")
      (node (ref "U1") (pin "142") (pinfunction "IO_L2P_0_142") (pintype "bidirectional"))
      (node (ref "U3") (pin "3") (pinfunction "A0_3") (pintype "input"))
    )
    (net (code "98") (name "/XA19") (class "Default")
      (node (ref "U1") (pin "105") (pinfunction "IO_L1P_1_105") (pintype "bidirectional"))
      (node (ref "U3") (pin "25") (pinfunction "A19_25") (pintype "input"))
    )
    (net (code "99") (name "/XA20") (class "Default")
      (node (ref "U1") (pin "143") (pinfunction "IO_L1N_VREF_0_143") (pintype "bidirectional"))
      (node (ref "U3") (pin "42") (pinfunction "A20_42") (pintype "input"))
    )
    (net (code "100") (name "/XD0") (class "Default")
      (node (ref "U1") (pin "132") (pinfunction "IO_L35P_GCLK17_0_132") (pintype "bidirectional"))
      (node (ref "U3") (pin "9") (pinfunction "I/O0_9") (pintype "bidirectional"))
    )
    (net (code "101") (name "/XD1") (class "Default")
      (node (ref "U1") (pin "127") (pinfunction "IO_L36P_GCLK15_0_127") (pintype "bidirectional"))
      (node (ref "U3") (pin "10") (pinfunction "I/O1_10") (pintype "bidirectional"))
    )
    (net (code "102") (name "/XD2") (class "Default")
      (node (ref "U1") (pin "124") (pinfunction "IO_L37P_GCLK13_0_124") (pintype "bidirectional"))
      (node (ref "U3") (pin "13") (pinfunction "I/O2_13") (pintype "bidirectional"))
    )
    (net (code "103") (name "/XD3") (class "Default")
      (node (ref "U1") (pin "123") (pinfunction "IO_L37N_GCLK12_0_123") (pintype "bidirectional"))
      (node (ref "U3") (pin "14") (pinfunction "I/O3_14") (pintype "bidirectional"))
    )
    (net (code "104") (name "/XD4") (class "Default")
      (node (ref "U1") (pin "115") (pinfunction "IO_L65P_SCP3_0_115") (pintype "bidirectional"))
      (node (ref "U3") (pin "31") (pinfunction "I/O4_31") (pintype "bidirectional"))
    )
    (net (code "105") (name "/XD5") (class "Default")
      (node (ref "U1") (pin "117") (pinfunction "IO_L64P_SCP5_0_117") (pintype "bidirectional"))
      (node (ref "U3") (pin "32") (pinfunction "I/O5_32") (pintype "bidirectional"))
    )
    (net (code "106") (name "/XD6") (class "Default")
      (node (ref "U1") (pin "119") (pinfunction "IO_L63P_SCP7_0_119") (pintype "bidirectional"))
      (node (ref "U3") (pin "35") (pinfunction "I/O6_35") (pintype "bidirectional"))
    )
    (net (code "107") (name "/XD7") (class "Default")
      (node (ref "U1") (pin "126") (pinfunction "IO_L36N_GCLK14_0_126") (pintype "bidirectional"))
      (node (ref "U3") (pin "36") (pinfunction "I/O7_36") (pintype "bidirectional"))
    )
    (net (code "108") (name "1.2V") (class "Default")
      (node (ref "C10") (pin "1") (pinfunction "1_1") (pintype "passive"))
      (node (ref "C11") (pin "1") (pinfunction "1_1") (pintype "passive"))
      (node (ref "C12") (pin "1") (pinfunction "1_1") (pintype "passive"))
      (node (ref "C19") (pin "1") (pinfunction "1_1") (pintype "passive"))
      (node (ref "C21") (pin "1") (pinfunction "1_1") (pintype "passive"))
      (node (ref "C9") (pin "1") (pinfunction "1_1") (pintype "passive"))
      (node (ref "U1") (pin "128") (pinfunction "VCCINT_128") (pintype "passive"))
      (node (ref "U1") (pin "19") (pinfunction "VCCINT_19") (pintype "passive"))
      (node (ref "U1") (pin "28") (pinfunction "VCCINT_28") (pintype "passive"))
      (node (ref "U1") (pin "52") (pinfunction "VCCINT_52") (pintype "passive"))
      (node (ref "U1") (pin "89") (pinfunction "VCCINT_89") (pintype "passive"))
      (node (ref "U7") (pin "2") (pinfunction "VOUT_2") (pintype "power_in"))
      (node (ref "U7") (pin "4") (pinfunction "TAB_4") (pintype "passive"))
    )
    (net (code "109") (name "3.3V") (class "Default")
      (node (ref "C15") (pin "1") (pinfunction "1_1") (pintype "passive"))
      (node (ref "C20") (pin "1") (pinfunction "1_1") (pintype "passive"))
      (node (ref "C22") (pin "1") (pinfunction "1_1") (pintype "passive"))
      (node (ref "C23") (pin "1") (pinfunction "1_1") (pintype "passive"))
      (node (ref "C24") (pin "1") (pinfunction "1_1") (pintype "passive"))
      (node (ref "C25") (pin "1") (pinfunction "1_1") (pintype "passive"))
      (node (ref "C26") (pin "1") (pinfunction "1_1") (pintype "passive"))
      (node (ref "C27") (pin "1") (pinfunction "1_1") (pintype "passive"))
      (node (ref "C28") (pin "1") (pinfunction "1_1") (pintype "passive"))
      (node (ref "C29") (pin "1") (pinfunction "1_1") (pintype "passive"))
      (node (ref "C30") (pin "1") (pinfunction "1_1") (pintype "passive"))
      (node (ref "C31") (pin "1") (pinfunction "1_1") (pintype "passive"))
      (node (ref "C32") (pin "1") (pinfunction "1_1") (pintype "passive"))
      (node (ref "C35") (pin "1") (pinfunction "1_1") (pintype "passive"))
      (node (ref "C36") (pin "1") (pinfunction "1_1") (pintype "passive"))
      (node (ref "J2") (pin "4") (pinfunction "4_4") (pintype "passive"))
      (node (ref "J5") (pin "2") (pinfunction "2_2") (pintype "passive"))
      (node (ref "J9") (pin "1") (pinfunction "1_1") (pintype "passive"))
      (node (ref "R10") (pin "2") (pinfunction "2_2") (pintype "passive"))
      (node (ref "R33") (pin "1") (pinfunction "1_1") (pintype "passive"))
      (node (ref "R34") (pin "1") (pinfunction "1_1") (pintype "passive"))
      (node (ref "R35") (pin "1") (pinfunction "1_1") (pintype "passive"))
      (node (ref "R6") (pin "1") (pinfunction "1_1") (pintype "passive"))
      (node (ref "R7") (pin "2") (pinfunction "2_2") (pintype "passive"))
      (node (ref "R8") (pin "2") (pinfunction "2_2") (pintype "passive"))
      (node (ref "R9") (pin "2") (pinfunction "2_2") (pintype "passive"))
      (node (ref "U1") (pin "103") (pinfunction "VCCO_1_103") (pintype "passive"))
      (node (ref "U1") (pin "122") (pinfunction "VCCO_0_122") (pintype "passive"))
      (node (ref "U1") (pin "125") (pinfunction "VCCO_0_125") (pintype "passive"))
      (node (ref "U1") (pin "129") (pinfunction "VCCAUX_129") (pintype "passive"))
      (node (ref "U1") (pin "135") (pinfunction "VCCO_0_135") (pintype "passive"))
      (node (ref "U1") (pin "18") (pinfunction "VCCO_3_18") (pintype "passive"))
      (node (ref "U1") (pin "20") (pinfunction "VCCAUX_20") (pintype "passive"))
      (node (ref "U1") (pin "31") (pinfunction "VCCO_3_31") (pintype "passive"))
      (node (ref "U1") (pin "36") (pinfunction "VCCAUX_36") (pintype "passive"))
      (node (ref "U1") (pin "4") (pinfunction "VCCO_3_4") (pintype "passive"))
      (node (ref "U1") (pin "42") (pinfunction "VCCO_2_42") (pintype "passive"))
      (node (ref "U1") (pin "53") (pinfunction "VCCAUX_53") (pintype "passive"))
      (node (ref "U1") (pin "63") (pinfunction "VCCO_2_63") (pintype "passive"))
      (node (ref "U1") (pin "69") (pinfunction "IO_L1N_M0_CMPMISO_2_69") (pintype "bidirectional"))
      (node (ref "U1") (pin "76") (pinfunction "VCCO_1_76") (pintype "passive"))
      (node (ref "U1") (pin "86") (pinfunction "VCCO_1_86") (pintype "passive"))
      (node (ref "U1") (pin "90") (pinfunction "VCCAUX_90") (pintype "passive"))
      (node (ref "U2") (pin "8") (pinfunction "VCC_8") (pintype "power_in"))
      (node (ref "U3") (pin "11") (pinfunction "VCC_11") (pintype "power_in"))
      (node (ref "U3") (pin "33") (pinfunction "VCC_33") (pintype "power_in"))
      (node (ref "U5") (pin "4") (pinfunction "VDD_4") (pintype "power_in"))
      (node (ref "U6") (pin "2") (pinfunction "VOUT_2") (pintype "power_in"))
      (node (ref "U6") (pin "4") (pinfunction "TAB_4") (pintype "passive"))
      (node (ref "U8") (pin "4") (pinfunction "VCCIO_4") (pintype "power_in"))
    )
    (net (code "110") (name "5V") (class "Default")
      (node (ref "C14") (pin "1") (pinfunction "1_1") (pintype "passive"))
      (node (ref "C18") (pin "1") (pinfunction "1_1") (pintype "passive"))
      (node (ref "C33") (pin "1") (pinfunction "1_1") (pintype "passive"))
      (node (ref "C34") (pin "1") (pinfunction "1_1") (pintype "passive"))
      (node (ref "J1") (pin "1") (pinfunction "1_1") (pintype "passive"))
      (node (ref "J5") (pin "1") (pinfunction "1_1") (pintype "passive"))
      (node (ref "J6") (pin "4") (pinfunction "4_4") (pintype "passive"))
      (node (ref "J7") (pin "1") (pinfunction "1_1") (pintype "passive"))
      (node (ref "R11") (pin "1") (pinfunction "1_1") (pintype "passive"))
      (node (ref "R32") (pin "2") (pinfunction "2_2") (pintype "passive"))
      (node (ref "U4") (pin "14") (pinfunction "DPOS_14") (pintype "input"))
      (node (ref "U4") (pin "15") (pinfunction "VSYNC_15") (pintype "input"))
      (node (ref "U4") (pin "4") (pinfunction "APOS_4") (pintype "input"))
      (node (ref "U4") (pin "5") (pinfunction "ENCD_5") (pintype "input"))
      (node (ref "U6") (pin "3") (pinfunction "VIN_3") (pintype "power_in"))
      (node (ref "U7") (pin "3") (pinfunction "VIN_3") (pintype "power_in"))
      (node (ref "U8") (pin "20") (pinfunction "VCC_20") (pintype "power_in"))
    )
    (net (code "111") (name "GND") (class "Default")
      (node (ref "C1") (pin "2") (pinfunction "2_2") (pintype "passive"))
      (node (ref "C10") (pin "2") (pinfunction "2_2") (pintype "passive"))
      (node (ref "C11") (pin "2") (pinfunction "2_2") (pintype "passive"))
      (node (ref "C12") (pin "2") (pinfunction "2_2") (pintype "passive"))
      (node (ref "C14") (pin "2") (pinfunction "2_2") (pintype "passive"))
      (node (ref "C15") (pin "2") (pinfunction "2_2") (pintype "passive"))
      (node (ref "C18") (pin "2") (pinfunction "2_2") (pintype "passive"))
      (node (ref "C19") (pin "2") (pinfunction "2_2") (pintype "passive"))
      (node (ref "C2") (pin "1") (pinfunction "1_1") (pintype "passive"))
      (node (ref "C20") (pin "2") (pinfunction "2_2") (pintype "passive"))
      (node (ref "C21") (pin "2") (pinfunction "2_2") (pintype "passive"))
      (node (ref "C22") (pin "2") (pinfunction "2_2") (pintype "passive"))
      (node (ref "C23") (pin "2") (pinfunction "2_2") (pintype "passive"))
      (node (ref "C24") (pin "2") (pinfunction "2_2") (pintype "passive"))
      (node (ref "C25") (pin "2") (pinfunction "2_2") (pintype "passive"))
      (node (ref "C26") (pin "2") (pinfunction "2_2") (pintype "passive"))
      (node (ref "C27") (pin "2") (pinfunction "2_2") (pintype "passive"))
      (node (ref "C28") (pin "2") (pinfunction "2_2") (pintype "passive"))
      (node (ref "C29") (pin "2") (pinfunction "2_2") (pintype "passive"))
      (node (ref "C3") (pin "1") (pinfunction "1_1") (pintype "passive"))
      (node (ref "C30") (pin "2") (pinfunction "2_2") (pintype "passive"))
      (node (ref "C31") (pin "2") (pinfunction "2_2") (pintype "passive"))
      (node (ref "C32") (pin "2") (pinfunction "2_2") (pintype "passive"))
      (node (ref "C33") (pin "2") (pinfunction "2_2") (pintype "passive"))
      (node (ref "C34") (pin "2") (pinfunction "2_2") (pintype "passive"))
      (node (ref "C35") (pin "2") (pinfunction "2_2") (pintype "passive"))
      (node (ref "C36") (pin "2") (pinfunction "2_2") (pintype "passive"))
      (node (ref "C37") (pin "2") (pinfunction "2_2") (pintype "passive"))
      (node (ref "C4") (pin "1") (pinfunction "1_1") (pintype "passive"))
      (node (ref "C9") (pin "2") (pinfunction "2_2") (pintype "passive"))
      (node (ref "D1") (pin "1") (pinfunction "A_1") (pintype "passive"))
      (node (ref "D2") (pin "2") (pinfunction "K_2") (pintype "passive"))
      (node (ref "J1") (pin "5") (pinfunction "5_5") (pintype "passive"))
      (node (ref "J2") (pin "6") (pinfunction "6_6") (pintype "passive"))
      (node (ref "J4") (pin "1") (pinfunction "S_1") (pintype "passive"))
      (node (ref "J5") (pin "39") (pinfunction "39_39") (pintype "passive"))
      (node (ref "J5") (pin "40") (pinfunction "40_40") (pintype "passive"))
      (node (ref "J6") (pin "3") (pinfunction "3_3") (pintype "passive"))
      (node (ref "J6") (pin "M1") (pinfunction "GND_M1") (pintype "power_in"))
      (node (ref "J6") (pin "M2") (pinfunction "GND_M2") (pintype "power_in"))
      (node (ref "J6") (pin "M3") (pinfunction "GND_M3") (pintype "power_in"))
      (node (ref "J7") (pin "4") (pinfunction "4_4") (pintype "passive"))
      (node (ref "J7") (pin "5") (pinfunction "5_5") (pintype "passive"))
      (node (ref "J7") (pin "6") (pinfunction "6_6") (pintype "passive"))
      (node (ref "J8") (pin "10") (pinfunction "10_10") (pintype "passive"))
      (node (ref "J8") (pin "6") (pinfunction "6_6") (pintype "passive"))
      (node (ref "J8") (pin "7") (pinfunction "7_7") (pintype "passive"))
      (node (ref "J8") (pin "8") (pinfunction "8_8") (pintype "passive"))
      (node (ref "J9") (pin "2") (pinfunction "2_2") (pintype "passive"))
      (node (ref "Q1") (pin "3") (pinfunction "EMITTER_3") (pintype "passive"))
      (node (ref "R28") (pin "1") (pinfunction "1_1") (pintype "passive"))
      (node (ref "R29") (pin "1") (pinfunction "1_1") (pintype "passive"))
      (node (ref "R3") (pin "2") (pinfunction "2_2") (pintype "passive"))
      (node (ref "R30") (pin "1") (pinfunction "1_1") (pintype "passive"))
      (node (ref "U1") (pin "108") (pinfunction "GND_108") (pintype "power_in"))
      (node (ref "U1") (pin "113") (pinfunction "GND_113") (pintype "power_in"))
      (node (ref "U1") (pin "13") (pinfunction "GND_13") (pintype "passive"))
      (node (ref "U1") (pin "130") (pinfunction "GND_130") (pintype "passive"))
      (node (ref "U1") (pin "136") (pinfunction "GND_136") (pintype "passive"))
      (node (ref "U1") (pin "144") (pinfunction "IO_L1P_HSWAPEN_0_144") (pintype "bidirectional"))
      (node (ref "U1") (pin "25") (pinfunction "GND_25") (pintype "passive"))
      (node (ref "U1") (pin "3") (pinfunction "GND_3") (pintype "passive"))
      (node (ref "U1") (pin "49") (pinfunction "GND_49") (pintype "passive"))
      (node (ref "U1") (pin "54") (pinfunction "GND_54") (pintype "passive"))
      (node (ref "U1") (pin "60") (pinfunction "IO_L13P_M1_2_60") (pintype "bidirectional"))
      (node (ref "U1") (pin "68") (pinfunction "GND_68") (pintype "passive"))
      (node (ref "U1") (pin "73") (pinfunction "SUSPEND_73") (pintype "passive"))
      (node (ref "U1") (pin "77") (pinfunction "GND_77") (pintype "power_in"))
      (node (ref "U1") (pin "91") (pinfunction "GND_91") (pintype "power_in"))
      (node (ref "U1") (pin "96") (pinfunction "GND_96") (pintype "power_in"))
      (node (ref "U2") (pin "4") (pinfunction "GND_4") (pintype "power_in"))
      (node (ref "U3") (pin "12") (pinfunction "GND_12") (pintype "power_in"))
      (node (ref "U3") (pin "34") (pinfunction "GND_34") (pintype "power_in"))
      (node (ref "U3") (pin "37") (pinfunction "~{OE}_37") (pintype "input"))
      (node (ref "U3") (pin "8") (pinfunction "~{CE}_8") (pintype "input"))
      (node (ref "U4") (pin "12") (pinfunction "SELECT_12") (pintype "input"))
      (node (ref "U4") (pin "13") (pinfunction "DGND_13") (pintype "input"))
      (node (ref "U4") (pin "2") (pinfunction "AGND_2") (pintype "input"))
      (node (ref "U5") (pin "2") (pinfunction "GND_2") (pintype "power_in"))
      (node (ref "U6") (pin "1") (pinfunction "GND_1") (pintype "power_in"))
      (node (ref "U7") (pin "1") (pinfunction "GND_1") (pintype "power_in"))
      (node (ref "U8") (pin "18") (pinfunction "GND_18") (pintype "power_in"))
      (node (ref "U8") (pin "21") (pinfunction "GND_21") (pintype "power_in"))
      (node (ref "U8") (pin "25") (pinfunction "AGND_25") (pintype "power_in"))
      (node (ref "U8") (pin "26") (pinfunction "TEST_26") (pintype "input"))
      (node (ref "U8") (pin "7") (pinfunction "GND_7") (pintype "power_in"))
      (node (ref "Y1") (pin "2") (pinfunction "OSC2_2") (pintype "passive"))
    )
    (net (code "112") (name "Net-(C3-Pad2)") (class "Default")
      (node (ref "C3") (pin "2") (pinfunction "2_2") (pintype "passive"))
      (node (ref "C39") (pin "1") (pinfunction "1_1") (pintype "passive"))
      (node (ref "R18") (pin "2") (pinfunction "2_2") (pintype "passive"))
    )
    (net (code "113") (name "Net-(C5-Pad1)") (class "Default")
      (node (ref "C5") (pin "1") (pinfunction "1_1") (pintype "passive"))
      (node (ref "R4") (pin "2") (pinfunction "2_2") (pintype "passive"))
    )
    (net (code "114") (name "Net-(C13-Pad2)") (class "Default")
      (node (ref "C13") (pin "2") (pinfunction "2_2") (pintype "passive"))
      (node (ref "R31") (pin "1") (pinfunction "1_1") (pintype "passive"))
    )
    (net (code "115") (name "Net-(C38-Pad1)") (class "Default")
      (node (ref "C38") (pin "1") (pinfunction "1_1") (pintype "passive"))
      (node (ref "C4") (pin "2") (pinfunction "2_2") (pintype "passive"))
      (node (ref "R17") (pin "2") (pinfunction "2_2") (pintype "passive"))
    )
    (net (code "116") (name "Net-(D1-K)") (class "Default")
      (node (ref "C2") (pin "2") (pinfunction "2_2") (pintype "passive"))
      (node (ref "C5") (pin "2") (pinfunction "2_2") (pintype "passive"))
      (node (ref "D1") (pin "2") (pinfunction "K_2") (pintype "passive"))
      (node (ref "R5") (pin "1") (pinfunction "1_1") (pintype "passive"))
    )
    (net (code "117") (name "Net-(D2-A)") (class "Default")
      (node (ref "D2") (pin "1") (pinfunction "A_1") (pintype "passive"))
      (node (ref "R11") (pin "2") (pinfunction "2_2") (pintype "passive"))
    )
    (net (code "118") (name "Net-(J6-Pad1)") (class "Default")
      (node (ref "J6") (pin "1") (pinfunction "1_1") (pintype "passive"))
      (node (ref "J7") (pin "2") (pinfunction "2_2") (pintype "passive"))
      (node (ref "R1") (pin "1") (pinfunction "1_1") (pintype "passive"))
    )
    (net (code "119") (name "Net-(J6-Pad5)") (class "Default")
      (node (ref "J6") (pin "5") (pinfunction "5_5") (pintype "passive"))
      (node (ref "J7") (pin "3") (pinfunction "3_3") (pintype "passive"))
      (node (ref "R2") (pin "1") (pinfunction "1_1") (pintype "passive"))
    )
    (net (code "120") (name "Net-(J8-Pad9)") (class "Default")
      (node (ref "J8") (pin "9") (pinfunction "9_9") (pintype "passive"))
      (node (ref "R35") (pin "2") (pinfunction "2_2") (pintype "passive"))
    )
    (net (code "121") (name "Net-(Q1-BASE)") (class "Default")
      (node (ref "Q1") (pin "2") (pinfunction "BASE_2") (pintype "input"))
      (node (ref "R5") (pin "2") (pinfunction "2_2") (pintype "passive"))
    )
    (net (code "122") (name "Net-(U1-DONE_2)") (class "Default")
      (node (ref "R9") (pin "1") (pinfunction "1_1") (pintype "passive"))
      (node (ref "U1") (pin "71") (pinfunction "DONE_2_71") (pintype "passive"))
    )
    (net (code "123") (name "Net-(U1-IO_L65P_INIT_B_2)") (class "Default")
      (node (ref "R7") (pin "1") (pinfunction "1_1") (pintype "passive"))
      (node (ref "U1") (pin "39") (pinfunction "IO_L65P_INIT_B_2_39") (pintype "bidirectional"))
    )
    (net (code "124") (name "Net-(U4-BIN)") (class "Default")
      (node (ref "C6") (pin "2") (pinfunction "2_2") (pintype "passive"))
      (node (ref "U4") (pin "8") (pinfunction "BIN_8") (pintype "input"))
    )
    (net (code "125") (name "Net-(U4-CMPS)") (class "Default")
      (node (ref "C13") (pin "1") (pinfunction "1_1") (pintype "passive"))
      (node (ref "U4") (pin "10") (pinfunction "CMPS_10") (pintype "output"))
    )
    (net (code "126") (name "Net-(U4-FIN)") (class "Default")
      (node (ref "C1") (pin "1") (pinfunction "1_1") (pintype "passive"))
      (node (ref "U4") (pin "3") (pinfunction "FIN_3") (pintype "input"))
      (node (ref "Y1") (pin "1") (pinfunction "OSC1_1") (pintype "passive"))
    )
    (net (code "127") (name "Net-(U4-GIN)") (class "Default")
      (node (ref "C7") (pin "2") (pinfunction "2_2") (pintype "passive"))
      (node (ref "U4") (pin "7") (pinfunction "GIN_7") (pintype "input"))
    )
    (net (code "128") (name "Net-(U4-RIN)") (class "Default")
      (node (ref "C8") (pin "2") (pinfunction "2_2") (pintype "passive"))
      (node (ref "U4") (pin "6") (pinfunction "RIN_6") (pintype "input"))
    )
    (net (code "129") (name "Net-(U8-3V3OUT)") (class "Default")
      (node (ref "C37") (pin "1") (pinfunction "1_1") (pintype "passive"))
      (node (ref "U8") (pin "17") (pinfunction "3V3OUT_17") (pintype "output"))
    )
    (net (code "130") (name "unconnected-(J1-Pad4)") (class "Default")
      (node (ref "J1") (pin "4") (pinfunction "4_4") (pintype "passive"))
    )
    (net (code "131") (name "unconnected-(J2-Pad1)") (class "Default")
      (node (ref "J2") (pin "1") (pinfunction "1_1") (pintype "passive"))
    )
    (net (code "132") (name "unconnected-(J2-Pad8)") (class "Default")
      (node (ref "J2") (pin "8") (pinfunction "8_8") (pintype "passive"))
    )
    (net (code "133") (name "unconnected-(J6-Pad2)") (class "Default")
      (node (ref "J6") (pin "2") (pinfunction "2_2") (pintype "passive"))
    )
    (net (code "134") (name "unconnected-(J6-Pad6)") (class "Default")
      (node (ref "J6") (pin "6") (pinfunction "6_6") (pintype "passive"))
    )
    (net (code "135") (name "unconnected-(J8-Pad4)") (class "Default")
      (node (ref "J8") (pin "4") (pinfunction "4_4") (pintype "passive"))
    )
    (net (code "136") (name "unconnected-(J8-Pad5)") (class "Default")
      (node (ref "J8") (pin "5") (pinfunction "5_5") (pintype "passive"))
    )
    (net (code "137") (name "unconnected-(J8-Pad11)") (class "Default")
      (node (ref "J8") (pin "11") (pinfunction "11_11") (pintype "passive"))
    )
    (net (code "138") (name "unconnected-(J8-Pad12)") (class "Default")
      (node (ref "J8") (pin "12") (pinfunction "12_12") (pintype "passive"))
    )
    (net (code "139") (name "unconnected-(J8-Pad15)") (class "Default")
      (node (ref "J8") (pin "15") (pinfunction "15_15") (pintype "passive"))
    )
    (net (code "140") (name "unconnected-(U1-CMPCS_B_2-Pad72)") (class "Default")
      (node (ref "U1") (pin "72") (pinfunction "CMPCS_B_2_72") (pintype "passive"))
    )
    (net (code "141") (name "unconnected-(U1-IO_L2N_CMPMOSI_2-Pad66)") (class "Default")
      (node (ref "U1") (pin "66") (pinfunction "IO_L2N_CMPMOSI_2_66") (pintype "bidirectional"))
    )
    (net (code "142") (name "unconnected-(U1-IO_L2P_CMPCLK_2-Pad67)") (class "Default")
      (node (ref "U1") (pin "67") (pinfunction "IO_L2P_CMPCLK_2_67") (pintype "bidirectional"))
    )
    (net (code "143") (name "unconnected-(U1-IO_L14N_D12_2-Pad57)") (class "Default")
      (node (ref "U1") (pin "57") (pinfunction "IO_L14N_D12_2_57") (pintype "bidirectional"))
    )
    (net (code "144") (name "unconnected-(U1-IO_L14P_D11_2-Pad58)") (class "Default")
      (node (ref "U1") (pin "58") (pinfunction "IO_L14P_D11_2_58") (pintype "bidirectional"))
    )
    (net (code "145") (name "unconnected-(U1-IO_L30P_GCLK1_D13_2-Pad56)") (class "Default")
      (node (ref "U1") (pin "56") (pinfunction "IO_L30P_GCLK1_D13_2_56") (pintype "bidirectional"))
    )
    (net (code "146") (name "unconnected-(U1-IO_L34N_1-Pad97)") (class "Default")
      (node (ref "U1") (pin "97") (pinfunction "IO_L34N_1_97") (pintype "bidirectional"))
    )
    (net (code "147") (name "unconnected-(U1-IO_L40P_GCLK11_1-Pad95)") (class "Default")
      (node (ref "U1") (pin "95") (pinfunction "IO_L40P_GCLK11_1_95") (pintype "bidirectional"))
    )
    (net (code "148") (name "unconnected-(U4-CRMA-Pad9)") (class "Default")
      (node (ref "U4") (pin "9") (pinfunction "CRMA_9") (pintype "output"))
    )
    (net (code "149") (name "unconnected-(U4-LUMA-Pad11)") (class "Default")
      (node (ref "U4") (pin "11") (pinfunction "LUMA_11") (pintype "output"))
    )
    (net (code "150") (name "unconnected-(U5-OE-Pad1)") (class "Default")
      (node (ref "U5") (pin "1") (pinfunction "OE_1") (pintype "passive"))
    )
    (net (code "151") (name "unconnected-(U8-D1-Pad5)") (class "Default")
      (node (ref "U8") (pin "5") (pinfunction "D1_5") (pintype "bidirectional"))
    )
    (net (code "152") (name "unconnected-(U8-D6-Pad10)") (class "Default")
      (node (ref "U8") (pin "10") (pinfunction "D6_10") (pintype "bidirectional"))
    )
    (net (code "153") (name "unconnected-(U8-D7-Pad6)") (class "Default")
      (node (ref "U8") (pin "6") (pinfunction "D7_6") (pintype "bidirectional"))
    )
    (net (code "154") (name "unconnected-(U8-PWREN#-Pad12)") (class "Default")
      (node (ref "U8") (pin "12") (pinfunction "PWREN#_12") (pintype "output"))
    )
    (net (code "155") (name "unconnected-(U8-RD#-Pad13)") (class "Default")
      (node (ref "U8") (pin "13") (pinfunction "RD#_13") (pintype "input"))
    )
    (net (code "156") (name "unconnected-(U8-RESET#-Pad19)") (class "Default")
      (node (ref "U8") (pin "19") (pinfunction "RESET#_19") (pintype "input"))
    )
    (net (code "157") (name "unconnected-(U8-RXF#-Pad23)") (class "Default")
      (node (ref "U8") (pin "23") (pinfunction "RXF#_23") (pintype "output"))
    )
    (net (code "158") (name "unconnected-(U8-TXE#-Pad22)") (class "Default")
      (node (ref "U8") (pin "22") (pinfunction "TXE#_22") (pintype "output"))
    )
    (net (code "159") (name "unconnected-(U8-WR-Pad14)") (class "Default")
      (node (ref "U8") (pin "14") (pinfunction "WR_14") (pintype "input"))
    )
    (net (code "160") (name "unconnected-(U8-XTIN-Pad27)") (class "Default")
      (node (ref "U8") (pin "27") (pinfunction "XTIN_27") (pintype "input"))
    )
    (net (code "161") (name "unconnected-(U8-XTOUT-Pad28)") (class "Default")
      (node (ref "U8") (pin "28") (pinfunction "XTOUT_28") (pintype "output"))
    )
  )
)
